# Regulateurs.net
KiCad netlist of a schematic drawn in Altium Designer
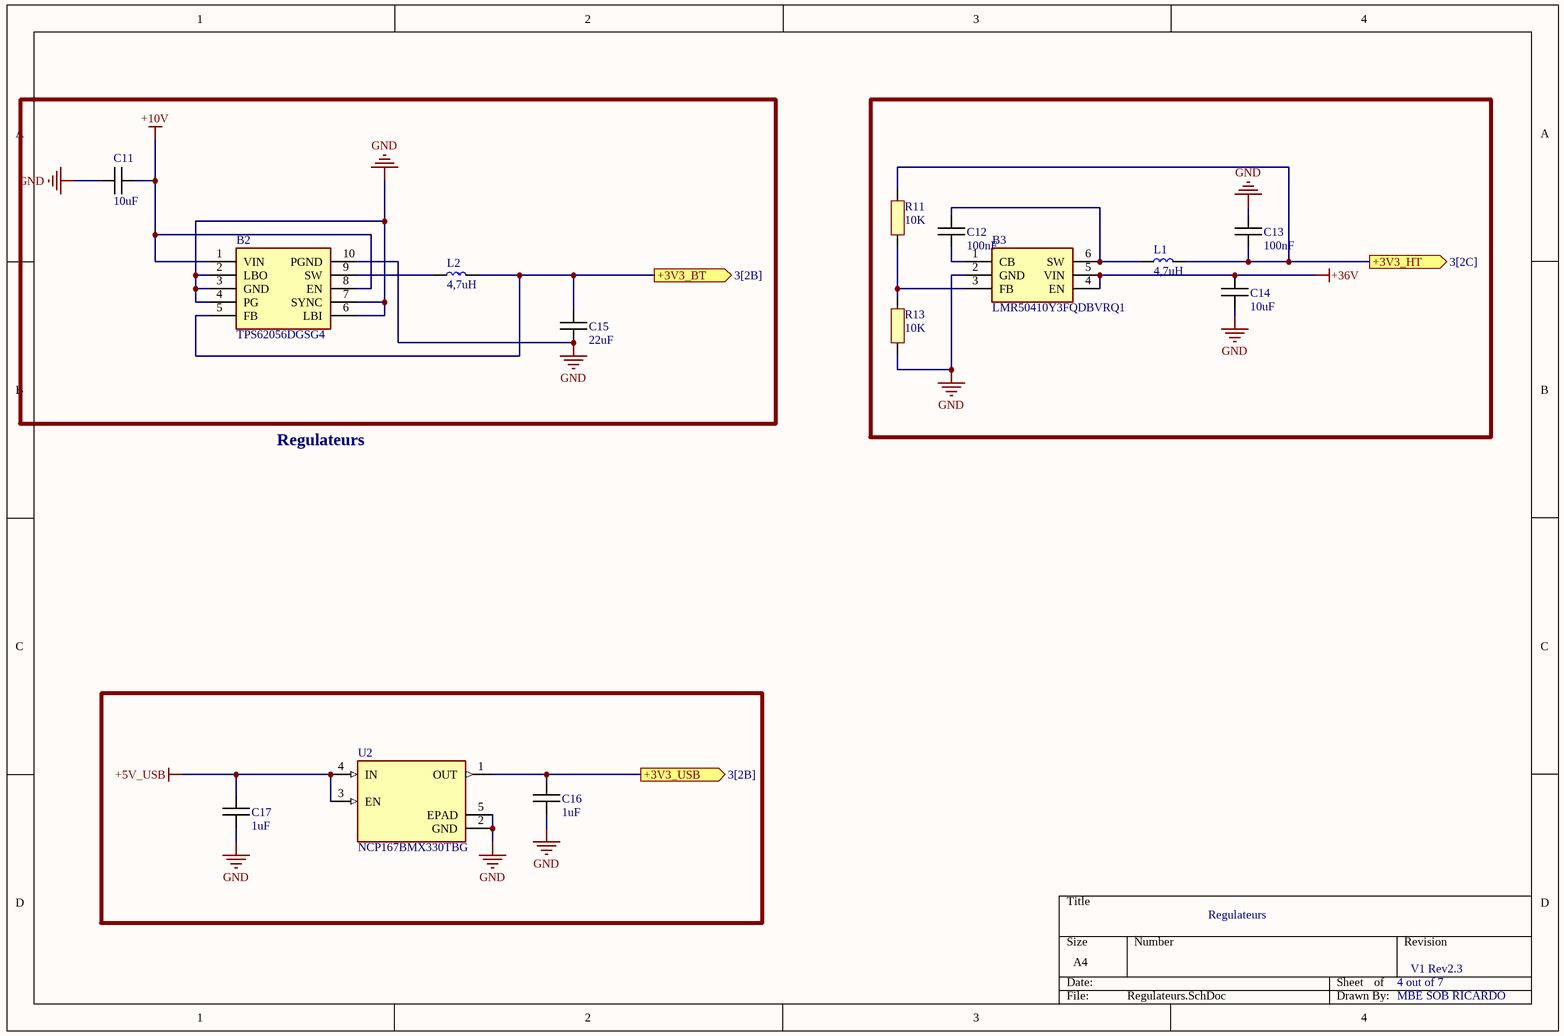
[diagram p0: Regulateurs.SchDoc]

(export (version "E")
  (design (tool "Eeschema 10.0.6"))
  (components
    (comp (ref "B2")
      (value "TPS62056DGSG4")
      (footprint "SOP50P490X110-10N")
      (fields (field (name "MOUSER PART NUMBER") "595-TPS62056DGSG4"))
      (libsource (lib "SCHLibrary") (part "TPS62056DGSG4"))
    )
    (comp (ref "B3")
      (value "LMR50410Y3FQDBVRQ1")
      (footprint "SOT95P280X145-6N")
      (fields (field (name "MOUSER PART NUMBER") "595-R50410Y3FQDBVRQ1"))
      (libsource (lib "SCHLibrary") (part "LMR50410Y3FQDBVRQ1"))
    )
    (comp (ref "C11")
      (value "10uF")
      (footprint "CAPC1005X06N")
      (libsource (lib "SCHLibrary") (part "Capacitor"))
    )
    (comp (ref "C12")
      (value "100nF")
      (footprint "CAPC1005X06N")
      (libsource (lib "SCHLibrary") (part "Capacitor"))
    )
    (comp (ref "C13")
      (value "100nF")
      (footprint "CAPC1005X06N")
      (libsource (lib "SCHLibrary") (part "Capacitor"))
    )
    (comp (ref "C14")
      (value "10uF")
      (footprint "CAPC1005X06N")
      (libsource (lib "SCHLibrary") (part "Capacitor"))
    )
    (comp (ref "C15")
      (value "22uF")
      (footprint "CAPC1005X06N")
      (libsource (lib "SCHLibrary") (part "Capacitor"))
    )
    (comp (ref "C16")
      (value "1uF")
      (footprint "CAPC1005X06N")
      (libsource (lib "SCHLibrary") (part "Capacitor"))
    )
    (comp (ref "C17")
      (value "1uF")
      (footprint "CAPC1005X06N")
      (libsource (lib "SCHLibrary") (part "Capacitor"))
    )
    (comp (ref "L1")
      (value "4,7uH")
      (footprint "LQPC1005X06N")
      (libsource (lib "SCHLibrary") (part "Bobine"))
    )
    (comp (ref "L2")
      (value "4,7uH")
      (footprint "LQPC1005X06N")
      (libsource (lib "SCHLibrary") (part "Bobine"))
    )
    (comp (ref "R11")
      (value "10K")
      (footprint "RESC1005X06N")
      (libsource (lib "SCHLibrary") (part "Resistor"))
    )
    (comp (ref "R13")
      (value "10K")
      (footprint "RESC1005X06N")
      (libsource (lib "SCHLibrary") (part "Resistor"))
    )
    (comp (ref "U2")
      (value "NCP167BMX330TBG")
      (footprint "NCP167BMX330TBG")
      (description "Régulateurs de tension LDO LDO 700 MA ULTRA-LOW NOISE 3.3V")
      (libsource (lib "SCHLibrary") (part "NCP167BMX330TBG"))
    )
  )
  (nets
    (net (code "1") (name "+5V_USB") (class "Default")
      (node (ref "C17") (pin "2") (pinfunction "2_2") (pintype "passive"))
      (node (ref "U2") (pin "3") (pinfunction "EN_3") (pintype "input"))
      (node (ref "U2") (pin "4") (pinfunction "IN_4") (pintype "input"))
    )
    (net (code "2") (name "+10V") (class "Default")
      (node (ref "B2") (pin "1") (pinfunction "VIN_1") (pintype "passive"))
      (node (ref "B2") (pin "8") (pinfunction "EN_8") (pintype "passive"))
      (node (ref "C11") (pin "1") (pinfunction "1_1") (pintype "passive"))
    )
    (net (code "3") (name "+36V") (class "Default")
      (node (ref "B3") (pin "4") (pinfunction "EN_4") (pintype "passive"))
      (node (ref "B3") (pin "5") (pinfunction "VIN_5") (pintype "passive"))
      (node (ref "C14") (pin "2") (pinfunction "2_2") (pintype "passive"))
    )
    (net (code "4") (name "/+3V3_BT") (class "Default")
      (node (ref "B2") (pin "5") (pinfunction "FB_5") (pintype "passive"))
      (node (ref "C15") (pin "1") (pinfunction "1_1") (pintype "passive"))
      (node (ref "L2") (pin "2") (pinfunction "2_2") (pintype "passive"))
    )
    (net (code "5") (name "/+3V3_HT") (class "Default")
      (node (ref "C13") (pin "1") (pinfunction "1_1") (pintype "passive"))
      (node (ref "L1") (pin "2") (pinfunction "2_2") (pintype "passive"))
      (node (ref "R11") (pin "2") (pinfunction "2_2") (pintype "passive"))
    )
    (net (code "6") (name "/+3V3_USB") (class "Default")
      (node (ref "C16") (pin "2") (pinfunction "2_2") (pintype "passive"))
      (node (ref "U2") (pin "1") (pinfunction "OUT_1") (pintype "output"))
    )
    (net (code "7") (name "GND") (class "Default")
      (node (ref "B2") (pin "10") (pinfunction "PGND_10") (pintype "passive"))
      (node (ref "B2") (pin "2") (pinfunction "LBO_2") (pintype "passive"))
      (node (ref "B2") (pin "3") (pinfunction "GND_3") (pintype "passive"))
      (node (ref "B2") (pin "4") (pinfunction "PG_4") (pintype "passive"))
      (node (ref "B2") (pin "6") (pinfunction "LBI_6") (pintype "passive"))
      (node (ref "B2") (pin "7") (pinfunction "SYNC_7") (pintype "passive"))
      (node (ref "B3") (pin "2") (pinfunction "GND_2") (pintype "passive"))
      (node (ref "C11") (pin "2") (pinfunction "2_2") (pintype "passive"))
      (node (ref "C13") (pin "2") (pinfunction "2_2") (pintype "passive"))
      (node (ref "C14") (pin "1") (pinfunction "1_1") (pintype "passive"))
      (node (ref "C15") (pin "2") (pinfunction "2_2") (pintype "passive"))
      (node (ref "C16") (pin "1") (pinfunction "1_1") (pintype "passive"))
      (node (ref "C17") (pin "1") (pinfunction "1_1") (pintype "passive"))
      (node (ref "R13") (pin "1") (pinfunction "1_1") (pintype "passive"))
      (node (ref "U2") (pin "2") (pinfunction "GND_2") (pintype "power_in"))
      (node (ref "U2") (pin "5") (pinfunction "EPAD_5") (pintype "power_in"))
    )
    (net (code "8") (name "Net-(B2-SW)") (class "Default")
      (node (ref "B2") (pin "9") (pinfunction "SW_9") (pintype "passive"))
      (node (ref "L2") (pin "1") (pinfunction "1_1") (pintype "passive"))
    )
    (net (code "9") (name "Net-(B3-CB)") (class "Default")
      (node (ref "B3") (pin "1") (pinfunction "CB_1") (pintype "passive"))
      (node (ref "C12") (pin "1") (pinfunction "1_1") (pintype "passive"))
    )
    (net (code "10") (name "Net-(B3-FB)") (class "Default")
      (node (ref "B3") (pin "3") (pinfunction "FB_3") (pintype "passive"))
      (node (ref "R11") (pin "1") (pinfunction "1_1") (pintype "passive"))
      (node (ref "R13") (pin "2") (pinfunction "2_2") (pintype "passive"))
    )
    (net (code "11") (name "Net-(B3-SW)") (class "Default")
      (node (ref "B3") (pin "6") (pinfunction "SW_6") (pintype "passive"))
      (node (ref "C12") (pin "2") (pinfunction "2_2") (pintype "passive"))
      (node (ref "L1") (pin "1") (pinfunction "1_1") (pintype "passive"))
    )
  )
)
